# laserrange_1_0_digital.net
KiCad netlist of a schematic drawn in EAGLE
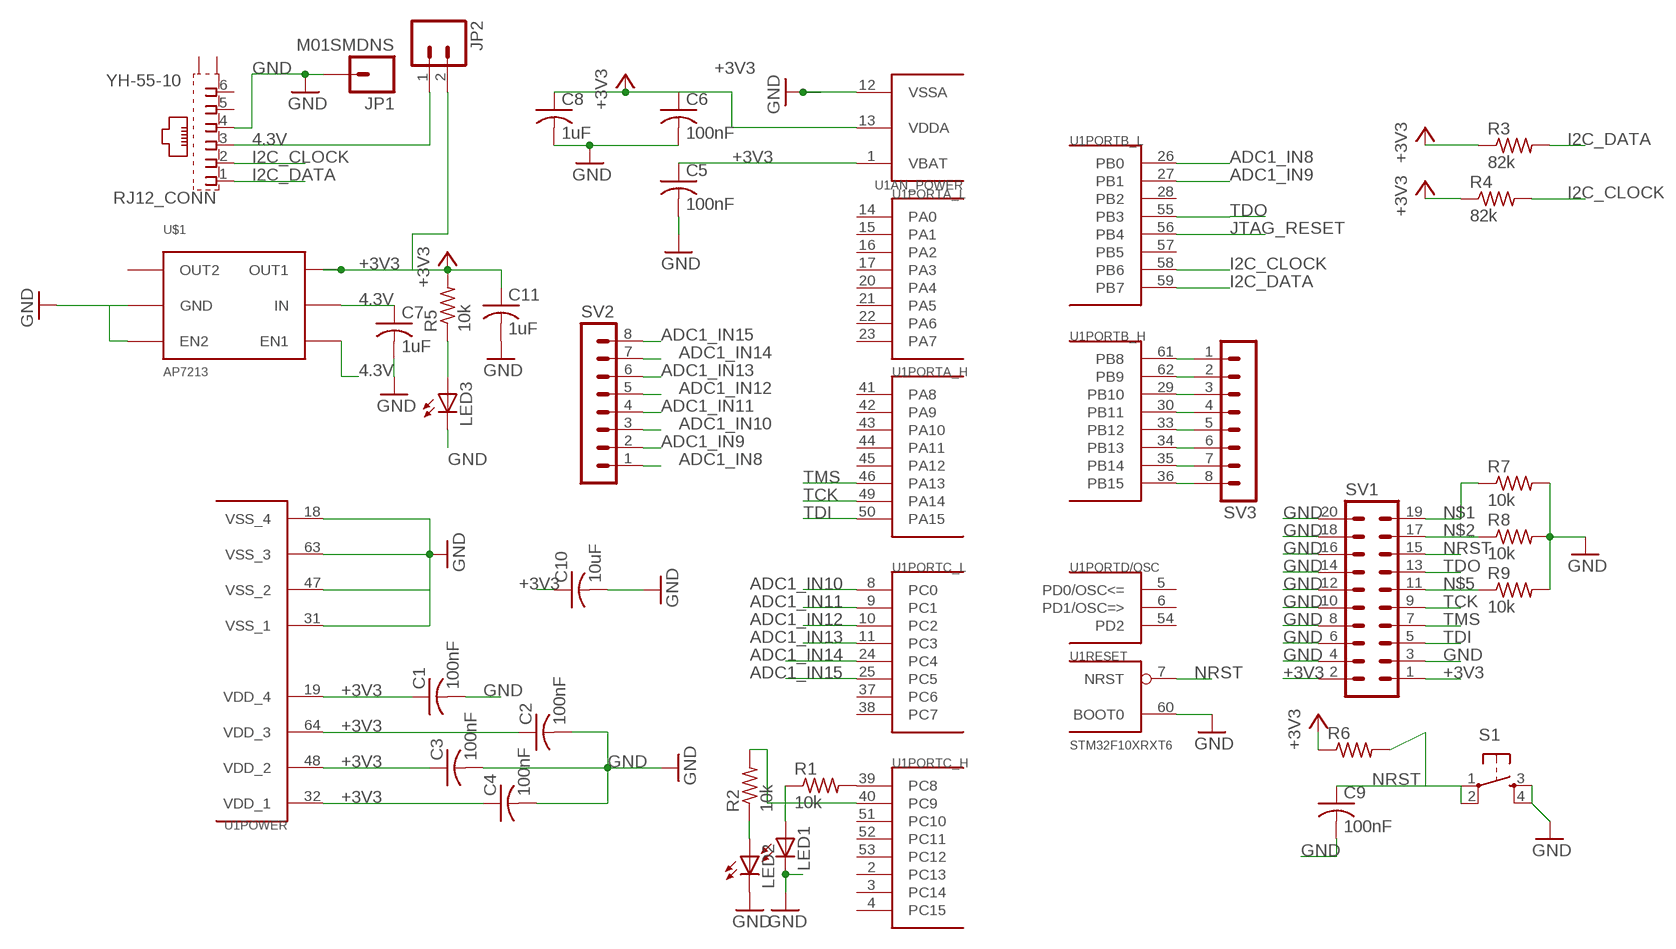
[diagram p0: schematic, sheet 1]

(export (version "E")
  (design (tool "Eeschema 10.0.6"))
  (components
    (comp (ref "C1")
      (value "100nF")
      (footprint "eagle-import:C0603")
      (libsource (lib "eagle-import") (part "C-USC0603"))
    )
    (comp (ref "C2")
      (value "100nF")
      (footprint "eagle-import:C0603")
      (libsource (lib "eagle-import") (part "C-USC0603"))
    )
    (comp (ref "C3")
      (value "100nF")
      (footprint "eagle-import:C0603")
      (libsource (lib "eagle-import") (part "C-USC0603"))
    )
    (comp (ref "C4")
      (value "100nF")
      (footprint "eagle-import:C0603")
      (libsource (lib "eagle-import") (part "C-USC0603"))
    )
    (comp (ref "C5")
      (value "100nF")
      (footprint "eagle-import:C0603")
      (libsource (lib "eagle-import") (part "C-USC0603"))
    )
    (comp (ref "C6")
      (value "100nF")
      (footprint "eagle-import:C0603")
      (libsource (lib "eagle-import") (part "C-USC0603"))
    )
    (comp (ref "C7")
      (value "1uF")
      (footprint "eagle-import:C0603")
      (libsource (lib "eagle-import") (part "C-USC0603"))
    )
    (comp (ref "C8")
      (value "1uF")
      (footprint "eagle-import:C0603")
      (libsource (lib "eagle-import") (part "C-USC0603"))
    )
    (comp (ref "C9")
      (value "100nF")
      (footprint "eagle-import:C0603")
      (libsource (lib "eagle-import") (part "C-USC0603"))
    )
    (comp (ref "C10")
      (value "10uF")
      (footprint "eagle-import:C0805")
      (libsource (lib "eagle-import") (part "resistor_C-USC0805"))
    )
    (comp (ref "C11")
      (value "1uF")
      (footprint "eagle-import:C0603")
      (libsource (lib "eagle-import") (part "C-USC0603"))
    )
    (comp (ref "JP1")
      (value "M01SMDNS")
      (footprint "eagle-import:1X01NS")
      (libsource (lib "eagle-import") (part "M01SMDNS"))
    )
    (comp (ref "JP2")
      (value "M02PTH")
      (footprint "eagle-import:1X02")
      (libsource (lib "eagle-import") (part "M02PTH"))
    )
    (comp (ref "LED1")
      (value "LEDCHIPLED_0805")
      (footprint "eagle-import:CHIPLED_0805")
      (libsource (lib "eagle-import") (part "LEDCHIPLED_0805"))
    )
    (comp (ref "LED2")
      (value "LEDCHIPLED_0805")
      (footprint "eagle-import:CHIPLED_0805")
      (libsource (lib "eagle-import") (part "LEDCHIPLED_0805"))
    )
    (comp (ref "LED3")
      (value "LEDCHIPLED_0805")
      (footprint "eagle-import:CHIPLED_0805")
      (libsource (lib "eagle-import") (part "LEDCHIPLED_0805"))
    )
    (comp (ref "R1")
      (value "10k")
      (footprint "eagle-import:R0805")
      (libsource (lib "eagle-import") (part "R-US_R0805"))
    )
    (comp (ref "R2")
      (value "10k")
      (footprint "eagle-import:R0805")
      (libsource (lib "eagle-import") (part "R-US_R0805"))
    )
    (comp (ref "R3")
      (value "82k")
      (footprint "eagle-import:R0805")
      (libsource (lib "eagle-import") (part "R-US_R0805"))
    )
    (comp (ref "R4")
      (value "82k")
      (footprint "eagle-import:R0805")
      (libsource (lib "eagle-import") (part "R-US_R0805"))
    )
    (comp (ref "R5")
      (value "10k")
      (footprint "eagle-import:R0805")
      (libsource (lib "eagle-import") (part "R-US_R0805"))
    )
    (comp (ref "R6")
      (value "R-US_R0805")
      (footprint "eagle-import:R0805")
      (libsource (lib "eagle-import") (part "R-US_R0805"))
    )
    (comp (ref "R7")
      (value "10k")
      (footprint "eagle-import:R0805")
      (libsource (lib "eagle-import") (part "R-US_R0805"))
    )
    (comp (ref "R8")
      (value "10k")
      (footprint "eagle-import:R0805")
      (libsource (lib "eagle-import") (part "R-US_R0805"))
    )
    (comp (ref "R9")
      (value "10k")
      (footprint "eagle-import:R0805")
      (libsource (lib "eagle-import") (part "R-US_R0805"))
    )
    (comp (ref "RJ12_CONN")
      (value "YH-55-10")
      (footprint "eagle-import:YH-55-10")
      (libsource (lib "eagle-import") (part "YH-55-10"))
    )
    (comp (ref "S1")
      (value "TAC_SWITCHPTH")
      (footprint "eagle-import:TACTILE-PTH")
      (libsource (lib "eagle-import") (part "TAC_SWITCHPTH"))
    )
    (comp (ref "SV1")
      (value "MA10-2")
      (footprint "eagle-import:MA10-2")
      (libsource (lib "eagle-import") (part "MA10-2"))
    )
    (comp (ref "SV2")
      (value "MA08-1")
      (footprint "eagle-import:MA08-1")
      (libsource (lib "eagle-import") (part "MA08-1"))
    )
    (comp (ref "SV3")
      (value "MA08-1")
      (footprint "eagle-import:MA08-1")
      (fields (field (name "OC_FARNELL") "unknown") (field (name "OC_NEWARK") "unknown"))
      (libsource (lib "eagle-import") (part "MA08-1"))
    )
    (comp (ref "U$1")
      (value "AP7213")
      (footprint "eagle-import:SOT23-6")
      (libsource (lib "eagle-import") (part "AP7213"))
    )
    (comp (ref "U1")
      (value "STM32F10XRXT6")
      (footprint "eagle-import:TQFP64")
      (libsource (lib "eagle-import") (part "STM32F10XRXT6"))
    )
  )
  (nets
    (net (code "1") (name "+3V3") (class "Default")
      (node (ref "C1") (pin "1") (pinfunction "1_1") (pintype "passive"))
      (node (ref "C10") (pin "1") (pinfunction "1_1") (pintype "passive"))
      (node (ref "C11") (pin "1") (pinfunction "1_1") (pintype "passive"))
      (node (ref "C2") (pin "1") (pinfunction "1_1") (pintype "passive"))
      (node (ref "C3") (pin "1") (pinfunction "1_1") (pintype "passive"))
      (node (ref "C4") (pin "1") (pinfunction "1_1") (pintype "passive"))
      (node (ref "C5") (pin "1") (pinfunction "1_1") (pintype "passive"))
      (node (ref "C6") (pin "1") (pinfunction "1_1") (pintype "passive"))
      (node (ref "C8") (pin "1") (pinfunction "1_1") (pintype "passive"))
      (node (ref "JP2") (pin "2") (pinfunction "2_2") (pintype "passive"))
      (node (ref "R3") (pin "1") (pinfunction "1_1") (pintype "passive"))
      (node (ref "R4") (pin "1") (pinfunction "1_1") (pintype "passive"))
      (node (ref "R5") (pin "2") (pinfunction "2_2") (pintype "passive"))
      (node (ref "R6") (pin "1") (pinfunction "1_1") (pintype "passive"))
      (node (ref "SV1") (pin "1") (pinfunction "1_1") (pintype "passive"))
      (node (ref "SV1") (pin "2") (pinfunction "2_2") (pintype "passive"))
      (node (ref "U$1") (pin "6") (pinfunction "OUT1_6") (pintype "bidirectional"))
      (node (ref "U1") (pin "1") (pinfunction "VBAT_1") (pintype "power_in"))
      (node (ref "U1") (pin "13") (pinfunction "VDDA_13") (pintype "power_in"))
      (node (ref "U1") (pin "19") (pinfunction "VDD_4_19") (pintype "power_in"))
      (node (ref "U1") (pin "32") (pinfunction "VDD_1_32") (pintype "power_in"))
      (node (ref "U1") (pin "48") (pinfunction "VDD_2_48") (pintype "power_in"))
      (node (ref "U1") (pin "64") (pinfunction "VDD_3_64") (pintype "power_in"))
    )
    (net (code "2") (name "/4.3V") (class "Default")
      (node (ref "C7") (pin "1") (pinfunction "1_1") (pintype "passive"))
      (node (ref "JP2") (pin "1") (pinfunction "1_1") (pintype "passive"))
      (node (ref "RJ12_CONN") (pin "3") (pinfunction "3_3") (pintype "passive"))
      (node (ref "U$1") (pin "4") (pinfunction "EN1_4") (pintype "bidirectional"))
      (node (ref "U$1") (pin "5") (pinfunction "IN_5") (pintype "bidirectional"))
    )
    (net (code "3") (name "/ADC1_IN8") (class "Default")
      (node (ref "SV2") (pin "1") (pinfunction "1_1") (pintype "passive"))
      (node (ref "U1") (pin "26") (pinfunction "PB0_26") (pintype "bidirectional"))
    )
    (net (code "4") (name "/ADC1_IN9") (class "Default")
      (node (ref "SV2") (pin "2") (pinfunction "2_2") (pintype "passive"))
      (node (ref "U1") (pin "27") (pinfunction "PB1_27") (pintype "bidirectional"))
    )
    (net (code "5") (name "/ADC1_IN10") (class "Default")
      (node (ref "SV2") (pin "3") (pinfunction "3_3") (pintype "passive"))
      (node (ref "U1") (pin "8") (pinfunction "PC0_8") (pintype "bidirectional"))
    )
    (net (code "6") (name "/ADC1_IN11") (class "Default")
      (node (ref "SV2") (pin "4") (pinfunction "4_4") (pintype "passive"))
      (node (ref "U1") (pin "9") (pinfunction "PC1_9") (pintype "bidirectional"))
    )
    (net (code "7") (name "/ADC1_IN12") (class "Default")
      (node (ref "SV2") (pin "5") (pinfunction "5_5") (pintype "passive"))
      (node (ref "U1") (pin "10") (pinfunction "PC2_10") (pintype "bidirectional"))
    )
    (net (code "8") (name "/ADC1_IN13") (class "Default")
      (node (ref "SV2") (pin "6") (pinfunction "6_6") (pintype "passive"))
      (node (ref "U1") (pin "11") (pinfunction "PC3_11") (pintype "bidirectional"))
    )
    (net (code "9") (name "/ADC1_IN14") (class "Default")
      (node (ref "SV2") (pin "7") (pinfunction "7_7") (pintype "passive"))
      (node (ref "U1") (pin "24") (pinfunction "PC4_24") (pintype "bidirectional"))
    )
    (net (code "10") (name "/ADC1_IN15") (class "Default")
      (node (ref "SV2") (pin "8") (pinfunction "8_8") (pintype "passive"))
      (node (ref "U1") (pin "25") (pinfunction "PC5_25") (pintype "bidirectional"))
    )
    (net (code "11") (name "/I2C_CLOCK") (class "Default")
      (node (ref "R4") (pin "2") (pinfunction "2_2") (pintype "passive"))
      (node (ref "RJ12_CONN") (pin "2") (pinfunction "2_2") (pintype "passive"))
      (node (ref "U1") (pin "58") (pinfunction "PB6_58") (pintype "bidirectional"))
    )
    (net (code "12") (name "/I2C_DATA") (class "Default")
      (node (ref "R3") (pin "2") (pinfunction "2_2") (pintype "passive"))
      (node (ref "RJ12_CONN") (pin "1") (pinfunction "1_1") (pintype "passive"))
      (node (ref "U1") (pin "59") (pinfunction "PB7_59") (pintype "bidirectional"))
    )
    (net (code "13") (name "/JTAG_RESET") (class "Default")
      (node (ref "U1") (pin "56") (pinfunction "PB4_56") (pintype "bidirectional"))
    )
    (net (code "14") (name "/N$1") (class "Default")
      (node (ref "R7") (pin "1") (pinfunction "1_1") (pintype "passive"))
      (node (ref "SV1") (pin "19") (pinfunction "19_19") (pintype "passive"))
    )
    (net (code "15") (name "/N$2") (class "Default")
      (node (ref "R8") (pin "1") (pinfunction "1_1") (pintype "passive"))
      (node (ref "SV1") (pin "17") (pinfunction "17_17") (pintype "passive"))
    )
    (net (code "16") (name "/N$5") (class "Default")
      (node (ref "R9") (pin "1") (pinfunction "1_1") (pintype "passive"))
      (node (ref "SV1") (pin "11") (pinfunction "11_11") (pintype "passive"))
    )
    (net (code "17") (name "/NRST") (class "Default")
      (node (ref "C9") (pin "1") (pinfunction "1_1") (pintype "passive"))
      (node (ref "R6") (pin "2") (pinfunction "2_2") (pintype "passive"))
      (node (ref "S1") (pin "1") (pinfunction "1_1") (pintype "passive"))
      (node (ref "S1") (pin "2") (pinfunction "2_2") (pintype "passive"))
      (node (ref "SV1") (pin "15") (pinfunction "15_15") (pintype "passive"))
      (node (ref "U1") (pin "7") (pinfunction "NRST_7") (pintype "input"))
    )
    (net (code "18") (name "/TCK") (class "Default")
      (node (ref "SV1") (pin "9") (pinfunction "9_9") (pintype "passive"))
      (node (ref "U1") (pin "49") (pinfunction "PA14_49") (pintype "bidirectional"))
    )
    (net (code "19") (name "/TDI") (class "Default")
      (node (ref "SV1") (pin "5") (pinfunction "5_5") (pintype "passive"))
      (node (ref "U1") (pin "50") (pinfunction "PA15_50") (pintype "bidirectional"))
    )
    (net (code "20") (name "/TDO") (class "Default")
      (node (ref "SV1") (pin "13") (pinfunction "13_13") (pintype "passive"))
      (node (ref "U1") (pin "55") (pinfunction "PB3_55") (pintype "bidirectional"))
    )
    (net (code "21") (name "/TMS") (class "Default")
      (node (ref "SV1") (pin "7") (pinfunction "7_7") (pintype "passive"))
      (node (ref "U1") (pin "46") (pinfunction "PA13_46") (pintype "bidirectional"))
    )
    (net (code "22") (name "GND") (class "Default")
      (node (ref "C1") (pin "2") (pinfunction "2_2") (pintype "passive"))
      (node (ref "C10") (pin "2") (pinfunction "2_2") (pintype "passive"))
      (node (ref "C11") (pin "2") (pinfunction "2_2") (pintype "passive"))
      (node (ref "C2") (pin "2") (pinfunction "2_2") (pintype "passive"))
      (node (ref "C3") (pin "2") (pinfunction "2_2") (pintype "passive"))
      (node (ref "C4") (pin "2") (pinfunction "2_2") (pintype "passive"))
      (node (ref "C5") (pin "2") (pinfunction "2_2") (pintype "passive"))
      (node (ref "C6") (pin "2") (pinfunction "2_2") (pintype "passive"))
      (node (ref "C7") (pin "2") (pinfunction "2_2") (pintype "passive"))
      (node (ref "C8") (pin "2") (pinfunction "2_2") (pintype "passive"))
      (node (ref "C9") (pin "2") (pinfunction "2_2") (pintype "passive"))
      (node (ref "JP1") (pin "1") (pinfunction "1_1") (pintype "passive"))
      (node (ref "LED1") (pin "C") (pinfunction "C_C") (pintype "passive"))
      (node (ref "LED2") (pin "C") (pinfunction "C_C") (pintype "passive"))
      (node (ref "LED3") (pin "C") (pinfunction "C_C") (pintype "passive"))
      (node (ref "R7") (pin "2") (pinfunction "2_2") (pintype "passive"))
      (node (ref "R8") (pin "2") (pinfunction "2_2") (pintype "passive"))
      (node (ref "R9") (pin "2") (pinfunction "2_2") (pintype "passive"))
      (node (ref "RJ12_CONN") (pin "4") (pinfunction "4_4") (pintype "passive"))
      (node (ref "S1") (pin "3") (pinfunction "3_3") (pintype "passive"))
      (node (ref "S1") (pin "4") (pinfunction "4_4") (pintype "passive"))
      (node (ref "SV1") (pin "10") (pinfunction "10_10") (pintype "passive"))
      (node (ref "SV1") (pin "12") (pinfunction "12_12") (pintype "passive"))
      (node (ref "SV1") (pin "14") (pinfunction "14_14") (pintype "passive"))
      (node (ref "SV1") (pin "16") (pinfunction "16_16") (pintype "passive"))
      (node (ref "SV1") (pin "18") (pinfunction "18_18") (pintype "passive"))
      (node (ref "SV1") (pin "20") (pinfunction "20_20") (pintype "passive"))
      (node (ref "SV1") (pin "3") (pinfunction "3_3") (pintype "passive"))
      (node (ref "SV1") (pin "4") (pinfunction "4_4") (pintype "passive"))
      (node (ref "SV1") (pin "6") (pinfunction "6_6") (pintype "passive"))
      (node (ref "SV1") (pin "8") (pinfunction "8_8") (pintype "passive"))
      (node (ref "U$1") (pin "2") (pinfunction "GND_2") (pintype "bidirectional"))
      (node (ref "U$1") (pin "3") (pinfunction "EN2_3") (pintype "bidirectional"))
      (node (ref "U1") (pin "12") (pinfunction "VSSA_12") (pintype "power_in"))
      (node (ref "U1") (pin "18") (pinfunction "VSS_4_18") (pintype "power_in"))
      (node (ref "U1") (pin "31") (pinfunction "VSS_1_31") (pintype "power_in"))
      (node (ref "U1") (pin "47") (pinfunction "VSS_2_47") (pintype "power_in"))
      (node (ref "U1") (pin "60") (pinfunction "BOOT0_60") (pintype "input"))
      (node (ref "U1") (pin "63") (pinfunction "VSS_3_63") (pintype "power_in"))
    )
    (net (code "23") (name "Net-(LED1-PadA)") (class "Default")
      (node (ref "LED1") (pin "A") (pinfunction "A_A") (pintype "passive"))
      (node (ref "R1") (pin "1") (pinfunction "1_1") (pintype "passive"))
    )
    (net (code "24") (name "Net-(LED2-PadA)") (class "Default")
      (node (ref "LED2") (pin "A") (pinfunction "A_A") (pintype "passive"))
      (node (ref "R2") (pin "1") (pinfunction "1_1") (pintype "passive"))
    )
    (net (code "25") (name "Net-(LED3-PadA)") (class "Default")
      (node (ref "LED3") (pin "A") (pinfunction "A_A") (pintype "passive"))
      (node (ref "R5") (pin "1") (pinfunction "1_1") (pintype "passive"))
    )
    (net (code "26") (name "Net-(U1D-PB8)") (class "Default")
      (node (ref "SV3") (pin "1") (pinfunction "1_1") (pintype "passive"))
      (node (ref "U1") (pin "61") (pinfunction "PB8_61") (pintype "bidirectional"))
    )
    (net (code "27") (name "Net-(U1D-PB9)") (class "Default")
      (node (ref "SV3") (pin "2") (pinfunction "2_2") (pintype "passive"))
      (node (ref "U1") (pin "62") (pinfunction "PB9_62") (pintype "bidirectional"))
    )
    (net (code "28") (name "Net-(U1D-PB10)") (class "Default")
      (node (ref "SV3") (pin "3") (pinfunction "3_3") (pintype "passive"))
      (node (ref "U1") (pin "29") (pinfunction "PB10_29") (pintype "bidirectional"))
    )
    (net (code "29") (name "Net-(U1D-PB11)") (class "Default")
      (node (ref "SV3") (pin "4") (pinfunction "4_4") (pintype "passive"))
      (node (ref "U1") (pin "30") (pinfunction "PB11_30") (pintype "bidirectional"))
    )
    (net (code "30") (name "Net-(U1D-PB12)") (class "Default")
      (node (ref "SV3") (pin "5") (pinfunction "5_5") (pintype "passive"))
      (node (ref "U1") (pin "33") (pinfunction "PB12_33") (pintype "bidirectional"))
    )
    (net (code "31") (name "Net-(U1D-PB13)") (class "Default")
      (node (ref "SV3") (pin "6") (pinfunction "6_6") (pintype "passive"))
      (node (ref "U1") (pin "34") (pinfunction "PB13_34") (pintype "bidirectional"))
    )
    (net (code "32") (name "Net-(U1D-PB14)") (class "Default")
      (node (ref "SV3") (pin "7") (pinfunction "7_7") (pintype "passive"))
      (node (ref "U1") (pin "35") (pinfunction "PB14_35") (pintype "bidirectional"))
    )
    (net (code "33") (name "Net-(U1D-PB15)") (class "Default")
      (node (ref "SV3") (pin "8") (pinfunction "8_8") (pintype "passive"))
      (node (ref "U1") (pin "36") (pinfunction "PB15_36") (pintype "bidirectional"))
    )
    (net (code "34") (name "Net-(U1F-PC8)") (class "Default")
      (node (ref "R1") (pin "2") (pinfunction "2_2") (pintype "passive"))
      (node (ref "U1") (pin "39") (pinfunction "PC8_39") (pintype "bidirectional"))
    )
    (net (code "35") (name "Net-(U1F-PC9)") (class "Default")
      (node (ref "R2") (pin "2") (pinfunction "2_2") (pintype "passive"))
      (node (ref "U1") (pin "40") (pinfunction "PC9_40") (pintype "bidirectional"))
    )
    (net (code "36") (name "unconnected-(RJ12_CONN-Pad5)") (class "Default")
      (node (ref "RJ12_CONN") (pin "5") (pinfunction "5_5") (pintype "passive"))
    )
    (net (code "37") (name "unconnected-(RJ12_CONN-Pad6)") (class "Default")
      (node (ref "RJ12_CONN") (pin "6") (pinfunction "6_6") (pintype "passive"))
    )
    (net (code "38") (name "unconnected-(RJ12_CONN-S-PadS1)") (class "Default")
      (node (ref "RJ12_CONN") (pin "S1") (pinfunction "S_S1") (pintype "passive"))
    )
    (net (code "39") (name "unconnected-(RJ12_CONN-S-PadS2)") (class "Default")
      (node (ref "RJ12_CONN") (pin "S2") (pinfunction "S_S2") (pintype "passive"))
    )
    (net (code "40") (name "unconnected-(U$1-OUT2-Pad1)") (class "Default")
      (node (ref "U$1") (pin "1") (pinfunction "OUT2_1") (pintype "bidirectional"))
    )
    (net (code "41") (name "unconnected-(U1B-PA8-Pad41)") (class "Default")
      (node (ref "U1") (pin "41") (pinfunction "PA8_41") (pintype "bidirectional"))
    )
    (net (code "42") (name "unconnected-(U1B-PA9-Pad42)") (class "Default")
      (node (ref "U1") (pin "42") (pinfunction "PA9_42") (pintype "bidirectional"))
    )
    (net (code "43") (name "unconnected-(U1B-PA10-Pad43)") (class "Default")
      (node (ref "U1") (pin "43") (pinfunction "PA10_43") (pintype "bidirectional"))
    )
    (net (code "44") (name "unconnected-(U1B-PA11-Pad44)") (class "Default")
      (node (ref "U1") (pin "44") (pinfunction "PA11_44") (pintype "bidirectional"))
    )
    (net (code "45") (name "unconnected-(U1B-PA12-Pad45)") (class "Default")
      (node (ref "U1") (pin "45") (pinfunction "PA12_45") (pintype "bidirectional"))
    )
    (net (code "46") (name "unconnected-(U1C-PA0-Pad14)") (class "Default")
      (node (ref "U1") (pin "14") (pinfunction "PA0_14") (pintype "bidirectional"))
    )
    (net (code "47") (name "unconnected-(U1C-PA1-Pad15)") (class "Default")
      (node (ref "U1") (pin "15") (pinfunction "PA1_15") (pintype "bidirectional"))
    )
    (net (code "48") (name "unconnected-(U1C-PA2-Pad16)") (class "Default")
      (node (ref "U1") (pin "16") (pinfunction "PA2_16") (pintype "bidirectional"))
    )
    (net (code "49") (name "unconnected-(U1C-PA3-Pad17)") (class "Default")
      (node (ref "U1") (pin "17") (pinfunction "PA3_17") (pintype "bidirectional"))
    )
    (net (code "50") (name "unconnected-(U1C-PA4-Pad20)") (class "Default")
      (node (ref "U1") (pin "20") (pinfunction "PA4_20") (pintype "bidirectional"))
    )
    (net (code "51") (name "unconnected-(U1C-PA5-Pad21)") (class "Default")
      (node (ref "U1") (pin "21") (pinfunction "PA5_21") (pintype "bidirectional"))
    )
    (net (code "52") (name "unconnected-(U1C-PA6-Pad22)") (class "Default")
      (node (ref "U1") (pin "22") (pinfunction "PA6_22") (pintype "bidirectional"))
    )
    (net (code "53") (name "unconnected-(U1C-PA7-Pad23)") (class "Default")
      (node (ref "U1") (pin "23") (pinfunction "PA7_23") (pintype "bidirectional"))
    )
    (net (code "54") (name "unconnected-(U1E-PB2-Pad28)") (class "Default")
      (node (ref "U1") (pin "28") (pinfunction "PB2_28") (pintype "bidirectional"))
    )
    (net (code "55") (name "unconnected-(U1E-PB5-Pad57)") (class "Default")
      (node (ref "U1") (pin "57") (pinfunction "PB5_57") (pintype "bidirectional"))
    )
    (net (code "56") (name "unconnected-(U1F-PC10-Pad51)") (class "Default")
      (node (ref "U1") (pin "51") (pinfunction "PC10_51") (pintype "bidirectional"))
    )
    (net (code "57") (name "unconnected-(U1F-PC11-Pad52)") (class "Default")
      (node (ref "U1") (pin "52") (pinfunction "PC11_52") (pintype "bidirectional"))
    )
    (net (code "58") (name "unconnected-(U1F-PC12-Pad53)") (class "Default")
      (node (ref "U1") (pin "53") (pinfunction "PC12_53") (pintype "bidirectional"))
    )
    (net (code "59") (name "unconnected-(U1F-PC13-Pad2)") (class "Default")
      (node (ref "U1") (pin "2") (pinfunction "PC13_2") (pintype "bidirectional"))
    )
    (net (code "60") (name "unconnected-(U1F-PC14-Pad3)") (class "Default")
      (node (ref "U1") (pin "3") (pinfunction "PC14_3") (pintype "bidirectional"))
    )
    (net (code "61") (name "unconnected-(U1F-PC15-Pad4)") (class "Default")
      (node (ref "U1") (pin "4") (pinfunction "PC15_4") (pintype "bidirectional"))
    )
    (net (code "62") (name "unconnected-(U1G-PC6-Pad37)") (class "Default")
      (node (ref "U1") (pin "37") (pinfunction "PC6_37") (pintype "bidirectional"))
    )
    (net (code "63") (name "unconnected-(U1G-PC7-Pad38)") (class "Default")
      (node (ref "U1") (pin "38") (pinfunction "PC7_38") (pintype "bidirectional"))
    )
    (net (code "64") (name "unconnected-(U1H-PD0{slash}OSC<=-Pad5)") (class "Default")
      (node (ref "U1") (pin "5") (pinfunction "PD0/OSC<=_5") (pintype "bidirectional"))
    )
    (net (code "65") (name "unconnected-(U1H-PD1{slash}OSC=>-Pad6)") (class "Default")
      (node (ref "U1") (pin "6") (pinfunction "PD1/OSC=>_6") (pintype "bidirectional"))
    )
    (net (code "66") (name "unconnected-(U1H-PD2-Pad54)") (class "Default")
      (node (ref "U1") (pin "54") (pinfunction "PD2_54") (pintype "bidirectional"))
    )
  )
)
